# Motors_Sheet.net
KiCad netlist of a schematic drawn in Altium Designer
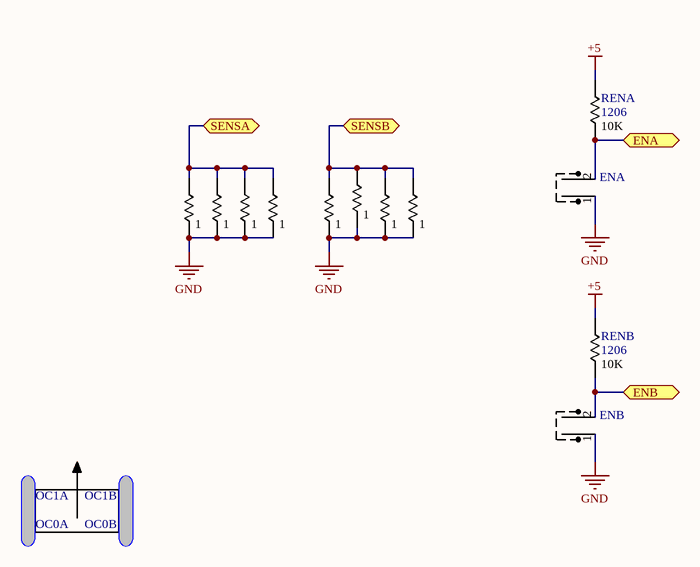
[diagram p0: Motors_Sheet.SchDoc]

(export (version "E")
  (design (tool "Eeschema 10.0.6"))
  (components
    (comp (ref "ENA") (value "jumper") (footprint "JUMPER2") (libsource (lib "JUMPER2") (part "Jumper_2")))
    (comp (ref "ENB") (value "jumper") (footprint "JUMPER2") (libsource (lib "JUMPER2") (part "Jumper_2")))
    (comp (ref "RENA")
      (value "1206")
      (footprint "1206")
      (fields (field (name "ALTIUM_VALUE") "10K"))
      (libsource (lib "Res_3_2__1_6") (part "1206"))
    )
    (comp (ref "RENB")
      (value "1206")
      (footprint "1206")
      (fields (field (name "ALTIUM_VALUE") "10K"))
      (libsource (lib "Res_3_2__1_6") (part "1206"))
    )
    (comp (ref "RS1")
      (value "1")
      (footprint "1206")
      (fields (field (name "Comment") "1206"))
      (libsource (lib "Res_3_2__1_6") (part "1206"))
    )
    (comp (ref "RS2")
      (value "1")
      (footprint "1206")
      (fields (field (name "Comment") "1206"))
      (libsource (lib "Res_3_2__1_6") (part "1206"))
    )
    (comp (ref "RS3")
      (value "1")
      (footprint "1206")
      (fields (field (name "Comment") "1206"))
      (libsource (lib "Res_3_2__1_6") (part "1206"))
    )
    (comp (ref "RS4")
      (value "1")
      (footprint "1206")
      (fields (field (name "Comment") "1206"))
      (libsource (lib "Res_3_2__1_6") (part "1206"))
    )
    (comp (ref "RS5")
      (value "1")
      (footprint "1206")
      (fields (field (name "Comment") "1206"))
      (libsource (lib "Res_3_2__1_6") (part "1206"))
    )
    (comp (ref "RS6")
      (value "1")
      (footprint "1206")
      (fields (field (name "Comment") "1206"))
      (libsource (lib "Res_3_2__1_6") (part "1206"))
    )
    (comp (ref "RS7")
      (value "1")
      (footprint "1206")
      (fields (field (name "Comment") "1206"))
      (libsource (lib "Res_3_2__1_6") (part "1206"))
    )
    (comp (ref "RS8")
      (value "1")
      (footprint "1206")
      (fields (field (name "Comment") "1206"))
      (libsource (lib "Res_3_2__1_6") (part "1206"))
    )
  )
  (nets
    (net (code "1") (name "+5") (class "Default")
      (node (ref "RENA") (pin "2") (pinfunction "2_2") (pintype "passive"))
      (node (ref "RENB") (pin "2") (pinfunction "2_2") (pintype "passive"))
    )
    (net (code "2") (name "/ENA") (class "Default")
      (node (ref "ENA") (pin "2") (pinfunction "2_2") (pintype "passive"))
      (node (ref "RENA") (pin "1") (pinfunction "1_1") (pintype "passive"))
    )
    (net (code "3") (name "/ENB") (class "Default")
      (node (ref "ENB") (pin "2") (pinfunction "2_2") (pintype "passive"))
      (node (ref "RENB") (pin "1") (pinfunction "1_1") (pintype "passive"))
    )
    (net (code "4") (name "/SENSA") (class "Default")
      (node (ref "RS1") (pin "2") (pinfunction "2_2") (pintype "passive"))
      (node (ref "RS2") (pin "2") (pinfunction "2_2") (pintype "passive"))
      (node (ref "RS3") (pin "2") (pinfunction "2_2") (pintype "passive"))
      (node (ref "RS4") (pin "2") (pinfunction "2_2") (pintype "passive"))
    )
    (net (code "5") (name "/SENSB") (class "Default")
      (node (ref "RS5") (pin "2") (pinfunction "2_2") (pintype "passive"))
      (node (ref "RS6") (pin "2") (pinfunction "2_2") (pintype "passive"))
      (node (ref "RS7") (pin "2") (pinfunction "2_2") (pintype "passive"))
      (node (ref "RS8") (pin "2") (pinfunction "2_2") (pintype "passive"))
    )
    (net (code "6") (name "GND") (class "Default")
      (node (ref "ENA") (pin "1") (pinfunction "1_1") (pintype "passive"))
      (node (ref "ENB") (pin "1") (pinfunction "1_1") (pintype "passive"))
      (node (ref "RS1") (pin "1") (pinfunction "1_1") (pintype "passive"))
      (node (ref "RS2") (pin "1") (pinfunction "1_1") (pintype "passive"))
      (node (ref "RS3") (pin "1") (pinfunction "1_1") (pintype "passive"))
      (node (ref "RS4") (pin "1") (pinfunction "1_1") (pintype "passive"))
      (node (ref "RS5") (pin "1") (pinfunction "1_1") (pintype "passive"))
      (node (ref "RS6") (pin "1") (pinfunction "1_1") (pintype "passive"))
      (node (ref "RS7") (pin "1") (pinfunction "1_1") (pintype "passive"))
      (node (ref "RS8") (pin "1") (pinfunction "1_1") (pintype "passive"))
    )
  )
)
